# PD85004_PP_PA.net
KiCad netlist of a schematic drawn in Altium Designer
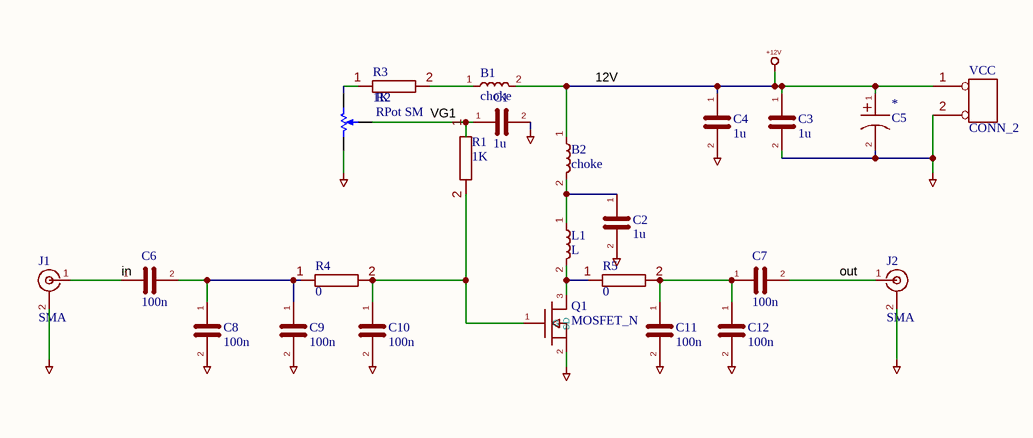
[diagram p0: PD85004_PP_PA.SchDoc]

(export (version "E")
  (design (tool "Eeschema 10.0.6"))
  (components
    (comp (ref "*") (value "C5") (footprint "CP") (libsource (lib "PD85004_PP_PA") (part "CP1")))
    (comp (ref "B1") (value "choke") (footprint "Choke") (libsource (lib "PD85004_PP_PA") (part "choke")))
    (comp (ref "B2") (value "choke") (footprint "Choke") (libsource (lib "PD85004_PP_PA") (part "choke")))
    (comp (ref "C1") (value "1u") (footprint "6-0805_L") (libsource (lib "PD85004_PP_PA") (part "C")))
    (comp (ref "C2") (value "1u") (footprint "6-0805_L") (libsource (lib "PD85004_PP_PA") (part "C")))
    (comp (ref "C3") (value "1u") (footprint "6-0805_L") (libsource (lib "PD85004_PP_PA") (part "C")))
    (comp (ref "C4") (value "1u") (footprint "6-0805_L") (libsource (lib "PD85004_PP_PA") (part "C")))
    (comp (ref "C6") (value "100n") (footprint "6-0805_L") (libsource (lib "PD85004_PP_PA") (part "C")))
    (comp (ref "C7") (value "100n") (footprint "6-0805_L") (libsource (lib "PD85004_PP_PA") (part "C")))
    (comp (ref "C8") (value "100n") (footprint "6-0805_L") (libsource (lib "PD85004_PP_PA") (part "C")))
    (comp (ref "C9") (value "100n") (footprint "6-0805_L") (libsource (lib "PD85004_PP_PA") (part "C")))
    (comp (ref "C10") (value "100n") (footprint "6-0805_L") (libsource (lib "PD85004_PP_PA") (part "C")))
    (comp (ref "C11") (value "100n") (footprint "6-0805_L") (libsource (lib "PD85004_PP_PA") (part "C")))
    (comp (ref "C12") (value "100n") (footprint "6-0805_L") (libsource (lib "PD85004_PP_PA") (part "C")))
    (comp (ref "J1") (value "SMA") (footprint "sma") (libsource (lib "") (part "SMA_1")))
    (comp (ref "J2") (value "SMA") (footprint "sma") (libsource (lib "PD85004_PP_PA") (part "SMA")))
    (comp (ref "L1") (value "L") (footprint "L") (libsource (lib "PD85004_PP_PA") (part "L")))
    (comp (ref "Q1")
      (value "MOSFET_N")
      (footprint "pd85004")
      (libsource (lib "PD85004_PP_PA") (part "MOSFET_N"))
    )
    (comp (ref "R1") (value "1K") (footprint "r") (libsource (lib "") (part "R_1")))
    (comp (ref "R2")
      (value "RPot SM")
      (footprint "POT4MM-2")
      (description "Square Trimming Potentiometer")
      (fields (field (name "PUBLISHER") "Altium Limited"))
      (libsource (lib "Miscellaneous Devices") (part "RPot SM"))
    )
    (comp (ref "R3") (value "1K") (footprint "r") (libsource (lib "PD85004_PP_PA") (part "R")))
    (comp (ref "R4") (value "0") (footprint "r") (libsource (lib "PD85004_PP_PA") (part "R")))
    (comp (ref "R5") (value "0") (footprint "r") (libsource (lib "PD85004_PP_PA") (part "R")))
    (comp (ref "VCC") (value "CONN_2") (footprint "con1") (libsource (lib "PD85004_PP_PA") (part "CONN_2")))
  )
  (nets
    (net (code "1") (name "+12V") (class "Default")
      (node (ref "*") (pin "1") (pinfunction "1_1") (pintype "passive"))
      (node (ref "B1") (pin "2") (pinfunction "2_2") (pintype "passive"))
      (node (ref "B2") (pin "1") (pinfunction "1_1") (pintype "passive"))
      (node (ref "C3") (pin "1") (pinfunction "1_1") (pintype "passive"))
      (node (ref "C4") (pin "1") (pinfunction "1_1") (pintype "passive"))
      (node (ref "VCC") (pin "1") (pinfunction "P1_1") (pintype "passive"))
    )
    (net (code "2") (name "/VG1") (class "Default")
      (node (ref "C1") (pin "1") (pinfunction "1_1") (pintype "passive"))
      (node (ref "R1") (pin "1") (pinfunction "1_1") (pintype "passive"))
      (node (ref "R2") (pin "W") (pinfunction "W_W") (pintype "passive"))
    )
    (net (code "3") (name "/in") (class "Default")
      (node (ref "C6") (pin "1") (pinfunction "1_1") (pintype "passive"))
      (node (ref "J1") (pin "1") (pinfunction "RF_1") (pintype "passive"))
    )
    (net (code "4") (name "/out") (class "Default")
      (node (ref "C7") (pin "2") (pinfunction "2_2") (pintype "passive"))
      (node (ref "J2") (pin "1") (pinfunction "RF_1") (pintype "passive"))
    )
    (net (code "5") (name "GND") (class "Default")
      (node (ref "*") (pin "2") (pinfunction "2_2") (pintype "passive"))
      (node (ref "C1") (pin "2") (pinfunction "2_2") (pintype "passive"))
      (node (ref "C10") (pin "2") (pinfunction "2_2") (pintype "passive"))
      (node (ref "C11") (pin "2") (pinfunction "2_2") (pintype "passive"))
      (node (ref "C12") (pin "2") (pinfunction "2_2") (pintype "passive"))
      (node (ref "C2") (pin "2") (pinfunction "2_2") (pintype "passive"))
      (node (ref "C3") (pin "2") (pinfunction "2_2") (pintype "passive"))
      (node (ref "C4") (pin "2") (pinfunction "2_2") (pintype "passive"))
      (node (ref "C8") (pin "2") (pinfunction "2_2") (pintype "passive"))
      (node (ref "C9") (pin "2") (pinfunction "2_2") (pintype "passive"))
      (node (ref "J1") (pin "2") (pinfunction "GND_2") (pintype "passive"))
      (node (ref "J2") (pin "2") (pinfunction "GND_2") (pintype "passive"))
      (node (ref "Q1") (pin "2") (pinfunction "S_2") (pintype "passive"))
      (node (ref "R2") (pin "CW") (pinfunction "+_CW") (pintype "passive"))
      (node (ref "VCC") (pin "2") (pinfunction "PM_2") (pintype "passive"))
    )
    (net (code "6") (name "Net-(B1-Pad1)") (class "Default")
      (node (ref "B1") (pin "1") (pinfunction "1_1") (pintype "passive"))
      (node (ref "R3") (pin "2") (pinfunction "2_2") (pintype "passive"))
    )
    (net (code "7") (name "Net-(B2-Pad2)") (class "Default")
      (node (ref "B2") (pin "2") (pinfunction "2_2") (pintype "passive"))
      (node (ref "C2") (pin "1") (pinfunction "1_1") (pintype "passive"))
      (node (ref "L1") (pin "1") (pinfunction "1_1") (pintype "passive"))
    )
    (net (code "8") (name "Net-(C6-Pad2)") (class "Default")
      (node (ref "C6") (pin "2") (pinfunction "2_2") (pintype "passive"))
      (node (ref "C8") (pin "1") (pinfunction "1_1") (pintype "passive"))
      (node (ref "C9") (pin "1") (pinfunction "1_1") (pintype "passive"))
      (node (ref "R4") (pin "1") (pinfunction "1_1") (pintype "passive"))
    )
    (net (code "9") (name "Net-(C11-Pad1)") (class "Default")
      (node (ref "C11") (pin "1") (pinfunction "1_1") (pintype "passive"))
      (node (ref "C12") (pin "1") (pinfunction "1_1") (pintype "passive"))
      (node (ref "C7") (pin "1") (pinfunction "1_1") (pintype "passive"))
      (node (ref "R5") (pin "2") (pinfunction "2_2") (pintype "passive"))
    )
    (net (code "10") (name "Net-(Q1-D)") (class "Default")
      (node (ref "L1") (pin "2") (pinfunction "2_2") (pintype "passive"))
      (node (ref "Q1") (pin "3") (pinfunction "D_3") (pintype "passive"))
      (node (ref "R5") (pin "1") (pinfunction "1_1") (pintype "passive"))
    )
    (net (code "11") (name "Net-(Q1-G)") (class "Default")
      (node (ref "C10") (pin "1") (pinfunction "1_1") (pintype "passive"))
      (node (ref "Q1") (pin "1") (pinfunction "G_1") (pintype "passive"))
      (node (ref "R1") (pin "2") (pinfunction "2_2") (pintype "passive"))
      (node (ref "R4") (pin "2") (pinfunction "2_2") (pintype "passive"))
    )
    (net (code "12") (name "Net-(R2--)") (class "Default")
      (node (ref "R2") (pin "CCW") (pinfunction "-_CCW") (pintype "passive"))
      (node (ref "R3") (pin "1") (pinfunction "1_1") (pintype "passive"))
    )
  )
)
